# L001-Static-Schematic.net
KiCad netlist of a schematic drawn in EAGLE
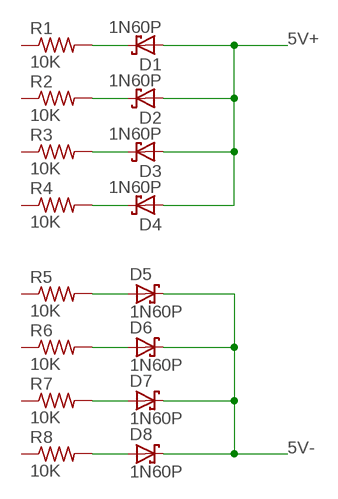
[diagram p0: schematic, sheet 1]

(export (version "E")
  (design (tool "Eeschema 10.0.6"))
  (components
    (comp (ref "D1")
      (value "1N60P")
      (footprint "eagle-import:DO41-7.6")
      (libsource (lib "eagle-import") (part "1N5817-B"))
    )
    (comp (ref "D2")
      (value "1N60P")
      (footprint "eagle-import:DO41-7.6")
      (libsource (lib "eagle-import") (part "1N5817-B"))
    )
    (comp (ref "D3")
      (value "1N60P")
      (footprint "eagle-import:DO41-7.6")
      (libsource (lib "eagle-import") (part "1N5817-B"))
    )
    (comp (ref "D4")
      (value "1N60P")
      (footprint "eagle-import:DO41-7.6")
      (libsource (lib "eagle-import") (part "1N5817-B"))
    )
    (comp (ref "D5")
      (value "1N60P")
      (footprint "eagle-import:DO41-7.6")
      (libsource (lib "eagle-import") (part "1N5817-B"))
    )
    (comp (ref "D6")
      (value "1N60P")
      (footprint "eagle-import:DO41-7.6")
      (libsource (lib "eagle-import") (part "1N5817-B"))
    )
    (comp (ref "D7")
      (value "1N60P")
      (footprint "eagle-import:DO41-7.6")
      (libsource (lib "eagle-import") (part "1N5817-B"))
    )
    (comp (ref "D8")
      (value "1N60P")
      (footprint "eagle-import:DO41-7.6")
      (libsource (lib "eagle-import") (part "1N5817-B"))
    )
    (comp (ref "R1")
      (value "10K")
      (footprint "eagle-import:VMTA55")
      (libsource (lib "eagle-import") (part "R-US_VMTA55"))
    )
    (comp (ref "R2")
      (value "10K")
      (footprint "eagle-import:VMTA55")
      (libsource (lib "eagle-import") (part "R-US_VMTA55"))
    )
    (comp (ref "R3")
      (value "10K")
      (footprint "eagle-import:VMTA55")
      (libsource (lib "eagle-import") (part "R-US_VMTA55"))
    )
    (comp (ref "R4")
      (value "10K")
      (footprint "eagle-import:VMTA55")
      (libsource (lib "eagle-import") (part "R-US_VMTA55"))
    )
    (comp (ref "R5")
      (value "10K")
      (footprint "eagle-import:VMTA55")
      (libsource (lib "eagle-import") (part "R-US_VMTA55"))
    )
    (comp (ref "R6")
      (value "10K")
      (footprint "eagle-import:VMTA55")
      (libsource (lib "eagle-import") (part "R-US_VMTA55"))
    )
    (comp (ref "R7")
      (value "10K")
      (footprint "eagle-import:VMTA55")
      (libsource (lib "eagle-import") (part "R-US_VMTA55"))
    )
    (comp (ref "R8")
      (value "10K")
      (footprint "eagle-import:VMTA55")
      (libsource (lib "eagle-import") (part "R-US_VMTA55"))
    )
  )
  (nets
    (net (code "1") (name "/5V+") (class "Default")
      (node (ref "D1") (pin "A") (pinfunction "A_A") (pintype "passive"))
      (node (ref "D2") (pin "A") (pinfunction "A_A") (pintype "passive"))
      (node (ref "D3") (pin "A") (pinfunction "A_A") (pintype "passive"))
      (node (ref "D4") (pin "A") (pinfunction "A_A") (pintype "passive"))
    )
    (net (code "2") (name "/5V-") (class "Default")
      (node (ref "D5") (pin "C") (pinfunction "C_C") (pintype "passive"))
      (node (ref "D6") (pin "C") (pinfunction "C_C") (pintype "passive"))
      (node (ref "D7") (pin "C") (pinfunction "C_C") (pintype "passive"))
      (node (ref "D8") (pin "C") (pinfunction "C_C") (pintype "passive"))
    )
    (net (code "3") (name "Net-(D1-PadC)") (class "Default")
      (node (ref "D1") (pin "C") (pinfunction "C_C") (pintype "passive"))
      (node (ref "R1") (pin "2") (pinfunction "2_2") (pintype "passive"))
    )
    (net (code "4") (name "Net-(D2-PadC)") (class "Default")
      (node (ref "D2") (pin "C") (pinfunction "C_C") (pintype "passive"))
      (node (ref "R2") (pin "2") (pinfunction "2_2") (pintype "passive"))
    )
    (net (code "5") (name "Net-(D3-PadC)") (class "Default")
      (node (ref "D3") (pin "C") (pinfunction "C_C") (pintype "passive"))
      (node (ref "R3") (pin "2") (pinfunction "2_2") (pintype "passive"))
    )
    (net (code "6") (name "Net-(D4-PadC)") (class "Default")
      (node (ref "D4") (pin "C") (pinfunction "C_C") (pintype "passive"))
      (node (ref "R4") (pin "2") (pinfunction "2_2") (pintype "passive"))
    )
    (net (code "7") (name "Net-(D5-PadA)") (class "Default")
      (node (ref "D5") (pin "A") (pinfunction "A_A") (pintype "passive"))
      (node (ref "R5") (pin "2") (pinfunction "2_2") (pintype "passive"))
    )
    (net (code "8") (name "Net-(D6-PadA)") (class "Default")
      (node (ref "D6") (pin "A") (pinfunction "A_A") (pintype "passive"))
      (node (ref "R6") (pin "2") (pinfunction "2_2") (pintype "passive"))
    )
    (net (code "9") (name "Net-(D7-PadA)") (class "Default")
      (node (ref "D7") (pin "A") (pinfunction "A_A") (pintype "passive"))
      (node (ref "R7") (pin "2") (pinfunction "2_2") (pintype "passive"))
    )
    (net (code "10") (name "Net-(D8-PadA)") (class "Default")
      (node (ref "D8") (pin "A") (pinfunction "A_A") (pintype "passive"))
      (node (ref "R8") (pin "2") (pinfunction "2_2") (pintype "passive"))
    )
    (net (code "11") (name "unconnected-(R1-Pad1)") (class "Default")
      (node (ref "R1") (pin "1") (pinfunction "1_1") (pintype "passive"))
    )
    (net (code "12") (name "unconnected-(R2-Pad1)") (class "Default")
      (node (ref "R2") (pin "1") (pinfunction "1_1") (pintype "passive"))
    )
    (net (code "13") (name "unconnected-(R3-Pad1)") (class "Default")
      (node (ref "R3") (pin "1") (pinfunction "1_1") (pintype "passive"))
    )
    (net (code "14") (name "unconnected-(R4-Pad1)") (class "Default")
      (node (ref "R4") (pin "1") (pinfunction "1_1") (pintype "passive"))
    )
    (net (code "15") (name "unconnected-(R5-Pad1)") (class "Default")
      (node (ref "R5") (pin "1") (pinfunction "1_1") (pintype "passive"))
    )
    (net (code "16") (name "unconnected-(R6-Pad1)") (class "Default")
      (node (ref "R6") (pin "1") (pinfunction "1_1") (pintype "passive"))
    )
    (net (code "17") (name "unconnected-(R7-Pad1)") (class "Default")
      (node (ref "R7") (pin "1") (pinfunction "1_1") (pintype "passive"))
    )
    (net (code "18") (name "unconnected-(R8-Pad1)") (class "Default")
      (node (ref "R8") (pin "1") (pinfunction "1_1") (pintype "passive"))
    )
  )
)
